# BUS.net
KiCad netlist of a schematic drawn in Altium Designer
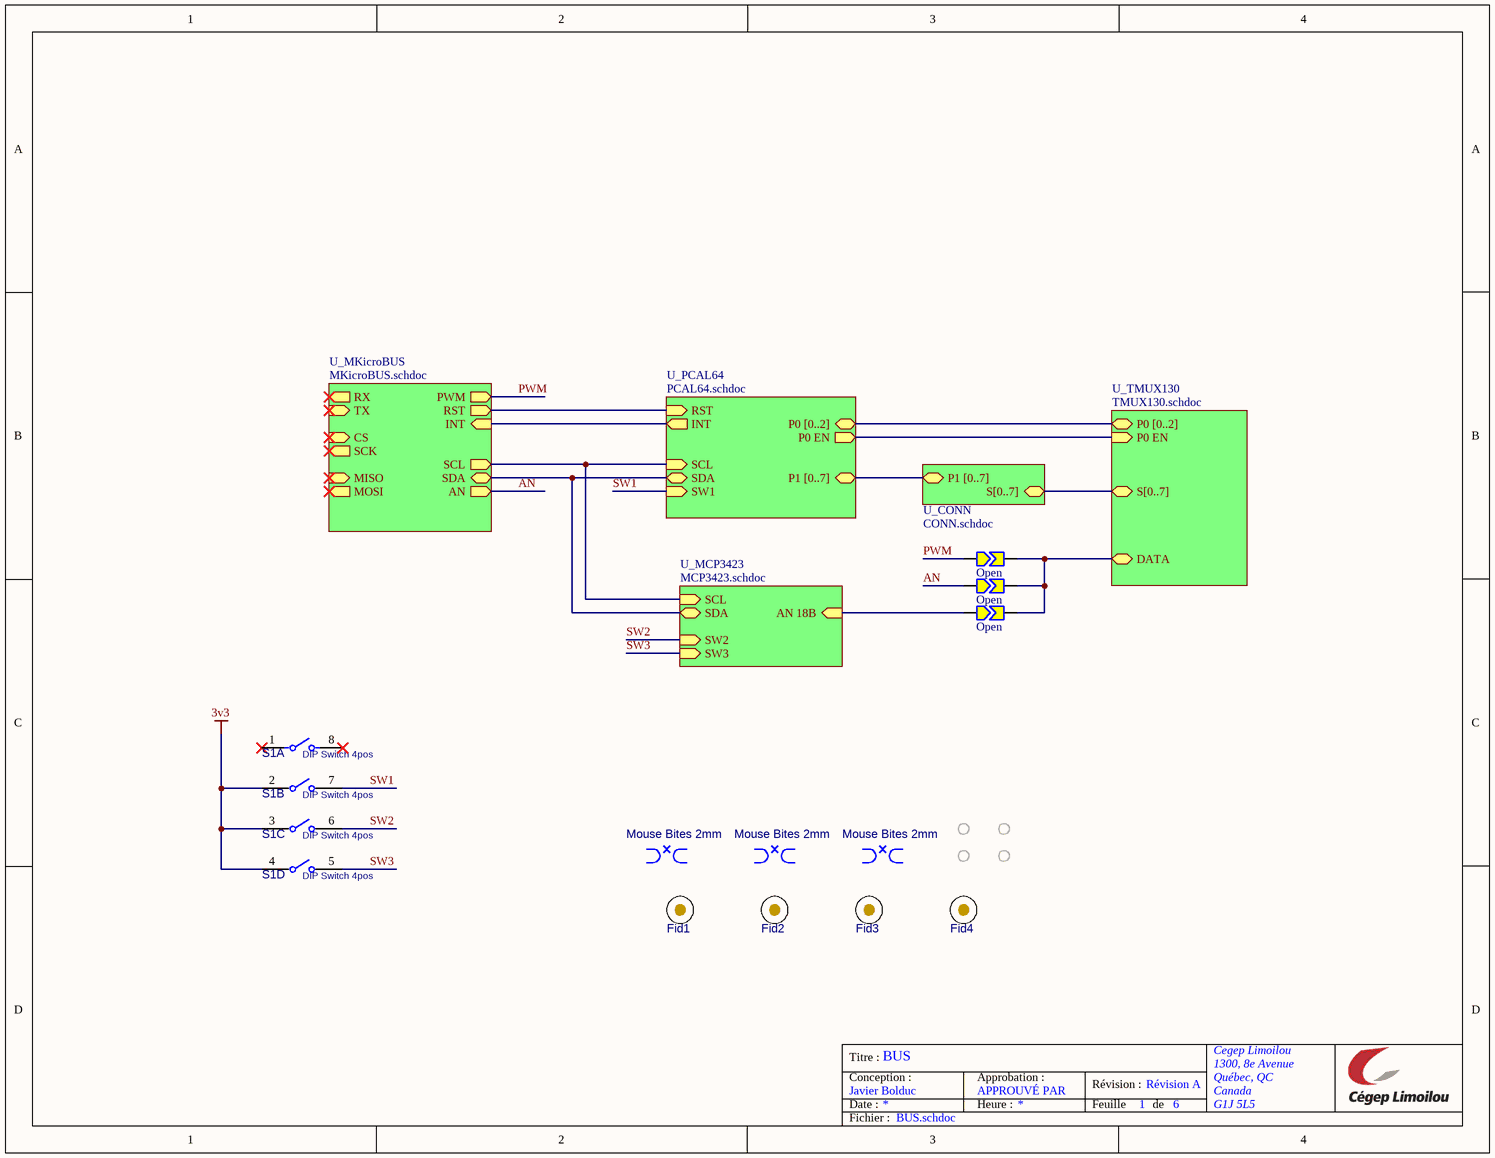
[diagram p0: BUS.schdoc]

(export (version "E")
  (design (tool "Eeschema 10.0.6"))
  (components
    (comp (ref "BRK1")
      (value "Mouse Bites 2mm")
      (footprint "BK_CRACK1B_M")
      (description "Mouse Bites")
      (fields (field (name "Comment") "DNP"))
      (libsource (lib "TEP-AltiumLib-Hardware") (part "BK_BREAKOUT_2MM"))
    )
    (comp (ref "BRK3")
      (value "Mouse Bites 2mm")
      (footprint "BK_CRACK1B_M")
      (description "Mouse Bites")
      (fields (field (name "Comment") "DNP"))
      (libsource (lib "TEP-AltiumLib-Hardware") (part "BK_BREAKOUT_2MM"))
    )
    (comp (ref "BRK4")
      (value "Mouse Bites 2mm")
      (footprint "BK_CRACK1B_M")
      (description "Mouse Bites")
      (fields (field (name "Comment") "DNP"))
      (libsource (lib "TEP-AltiumLib-Hardware") (part "BK_BREAKOUT_2MM"))
    )
    (comp (ref "Fid1")
      (value "DNP")
      (footprint "FD_Fiducial")
      (description "Fiducial mark for alignement and Pick&Place")
      (libsource (lib "TEP-AltiumLib-TP-MH-Tooling-Logo") (part "Fiducial"))
    )
    (comp (ref "Fid2")
      (value "DNP")
      (footprint "FD_Fiducial")
      (description "Fiducial mark for alignement and Pick&Place")
      (libsource (lib "TEP-AltiumLib-TP-MH-Tooling-Logo") (part "Fiducial"))
    )
    (comp (ref "Fid3")
      (value "DNP")
      (footprint "FD_Fiducial")
      (description "Fiducial mark for alignement and Pick&Place")
      (libsource (lib "TEP-AltiumLib-TP-MH-Tooling-Logo") (part "Fiducial"))
    )
    (comp (ref "Fid4")
      (value "DNP")
      (footprint "FD_Fiducial")
      (description "Fiducial mark for alignement and Pick&Place")
      (libsource (lib "TEP-AltiumLib-TP-MH-Tooling-Logo") (part "Fiducial"))
    )
    (comp (ref "MH1")
      (value "DNP")
      (footprint "MP_M-Hole_M2-NonPlated")
      (description "Mounting Hole 2mm non plated")
      (libsource (lib "TEP-AltiumLib-Hardware") (part "MH-2MM_NP"))
    )
    (comp (ref "MH2")
      (value "DNP")
      (footprint "MP_M-Hole_M2-NonPlated")
      (description "Mounting Hole 2mm non plated")
      (libsource (lib "TEP-AltiumLib-Hardware") (part "MH-2MM_NP"))
    )
    (comp (ref "MH3")
      (value "DNP")
      (footprint "MP_M-Hole_M2-NonPlated")
      (description "Mounting Hole 2mm non plated")
      (libsource (lib "TEP-AltiumLib-Hardware") (part "MH-2MM_NP"))
    )
    (comp (ref "MH4")
      (value "DNP")
      (footprint "MP_M-Hole_M2-NonPlated")
      (description "Mounting Hole 2mm non plated")
      (libsource (lib "TEP-AltiumLib-Hardware") (part "MH-2MM_NP"))
    )
    (comp (ref "S1")
      (value "DIP Switch 4pos")
      (footprint "S_DIP_SWITCH_50MIL_4POS")
      (description "SWITCH DIP SLIDE SPST 25MA 24V, pitch 1.27mm, height 1.55mm")
      (fields (field (name "Comment") "DSHP04TSGER"))
      (libsource (lib "TEP-AltiumLib") (part "SW_DIP_50MIL_4POS"))
    )
    (comp (ref "SB1")
      (value "Open")
      (footprint "SB-TINY-OPEN")
      (description "Solder Jumper")
      (libsource (lib "TEP-AltiumLib-Hardware") (part "Solder-Jumper-Open"))
    )
    (comp (ref "SB2")
      (value "Open")
      (footprint "SB-TINY-OPEN")
      (description "Solder Jumper")
      (libsource (lib "TEP-AltiumLib-Hardware") (part "Solder-Jumper-Open"))
    )
    (comp (ref "SB3")
      (value "Open")
      (footprint "SB-TINY-OPEN")
      (description "Solder Jumper")
      (libsource (lib "TEP-AltiumLib-Hardware") (part "Solder-Jumper-Open"))
    )
  )
  (nets
    (net (code "1") (name "/AN") (class "Default")
      (node (ref "SB2") (pin "1") (pinfunction "1_1") (pintype "passive"))
    )
    (net (code "2") (name "/AN 18B") (class "Default")
      (node (ref "SB3") (pin "1") (pinfunction "1_1") (pintype "passive"))
    )
    (net (code "4") (name "/DATA") (class "Default")
      (node (ref "SB1") (pin "2") (pinfunction "2_2") (pintype "passive"))
      (node (ref "SB2") (pin "2") (pinfunction "2_2") (pintype "passive"))
      (node (ref "SB3") (pin "2") (pinfunction "2_2") (pintype "passive"))
    )
    (net (code "11") (name "/PWM") (class "Default")
      (node (ref "SB1") (pin "1") (pinfunction "1_1") (pintype "passive"))
    )
    (net (code "17") (name "/SW1") (class "Default")
      (node (ref "S1") (pin "7") (pinfunction "7_7") (pintype "passive"))
    )
    (net (code "18") (name "/SW2") (class "Default")
      (node (ref "S1") (pin "6") (pinfunction "6_6") (pintype "passive"))
    )
    (net (code "19") (name "/SW3") (class "Default")
      (node (ref "S1") (pin "5") (pinfunction "5_5") (pintype "passive"))
    )
    (net (code "22") (name "3v3") (class "Default")
      (node (ref "S1") (pin "2") (pinfunction "2_2") (pintype "passive"))
      (node (ref "S1") (pin "3") (pinfunction "3_3") (pintype "passive"))
      (node (ref "S1") (pin "4") (pinfunction "4_4") (pintype "passive"))
    )
    (net (code "23") (name "unconnected-(BRK1-Pad1)") (class "Default")
      (node (ref "BRK1") (pin "1") (pinfunction "1_1") (pintype "passive"))
    )
    (net (code "24") (name "unconnected-(BRK1-Pad2)") (class "Default")
      (node (ref "BRK1") (pin "2") (pinfunction "2_2") (pintype "passive"))
    )
    (net (code "25") (name "unconnected-(BRK1-Pad3)") (class "Default")
      (node (ref "BRK1") (pin "3") (pinfunction "3_3") (pintype "passive"))
    )
    (net (code "26") (name "unconnected-(BRK1-Pad4)") (class "Default")
      (node (ref "BRK1") (pin "4") (pinfunction "4_4") (pintype "passive"))
    )
    (net (code "27") (name "unconnected-(BRK1-Pad5)") (class "Default")
      (node (ref "BRK1") (pin "5") (pinfunction "5_5") (pintype "passive"))
    )
    (net (code "28") (name "unconnected-(BRK3-Pad1)") (class "Default")
      (node (ref "BRK3") (pin "1") (pinfunction "1_1") (pintype "passive"))
    )
    (net (code "29") (name "unconnected-(BRK3-Pad2)") (class "Default")
      (node (ref "BRK3") (pin "2") (pinfunction "2_2") (pintype "passive"))
    )
    (net (code "30") (name "unconnected-(BRK3-Pad3)") (class "Default")
      (node (ref "BRK3") (pin "3") (pinfunction "3_3") (pintype "passive"))
    )
    (net (code "31") (name "unconnected-(BRK3-Pad4)") (class "Default")
      (node (ref "BRK3") (pin "4") (pinfunction "4_4") (pintype "passive"))
    )
    (net (code "32") (name "unconnected-(BRK3-Pad5)") (class "Default")
      (node (ref "BRK3") (pin "5") (pinfunction "5_5") (pintype "passive"))
    )
    (net (code "33") (name "unconnected-(BRK4-Pad1)") (class "Default")
      (node (ref "BRK4") (pin "1") (pinfunction "1_1") (pintype "passive"))
    )
    (net (code "34") (name "unconnected-(BRK4-Pad2)") (class "Default")
      (node (ref "BRK4") (pin "2") (pinfunction "2_2") (pintype "passive"))
    )
    (net (code "35") (name "unconnected-(BRK4-Pad3)") (class "Default")
      (node (ref "BRK4") (pin "3") (pinfunction "3_3") (pintype "passive"))
    )
    (net (code "36") (name "unconnected-(BRK4-Pad4)") (class "Default")
      (node (ref "BRK4") (pin "4") (pinfunction "4_4") (pintype "passive"))
    )
    (net (code "37") (name "unconnected-(BRK4-Pad5)") (class "Default")
      (node (ref "BRK4") (pin "5") (pinfunction "5_5") (pintype "passive"))
    )
    (net (code "38") (name "unconnected-(Fid1-Pad1)") (class "Default")
      (node (ref "Fid1") (pin "1") (pinfunction "1_1") (pintype "passive"))
    )
    (net (code "39") (name "unconnected-(Fid1-Pad1)_1") (class "Default")
      (node (ref "Fid1") (pin "1") (pinfunction "1_1") (pintype "passive"))
    )
    (net (code "40") (name "unconnected-(Fid1-Pad2)") (class "Default")
      (node (ref "Fid1") (pin "2") (pinfunction "2_2") (pintype "passive"))
    )
    (net (code "41") (name "unconnected-(Fid1-Pad3)") (class "Default")
      (node (ref "Fid1") (pin "3") (pinfunction "3_3") (pintype "passive"))
    )
    (net (code "42") (name "unconnected-(Fid1-Pad4)") (class "Default")
      (node (ref "Fid1") (pin "4") (pinfunction "4_4") (pintype "passive"))
    )
    (net (code "43") (name "unconnected-(Fid1-Pad5)") (class "Default")
      (node (ref "Fid1") (pin "5") (pinfunction "5_5") (pintype "passive"))
    )
    (net (code "44") (name "unconnected-(Fid2-Pad1)") (class "Default")
      (node (ref "Fid2") (pin "1") (pinfunction "1_1") (pintype "passive"))
    )
    (net (code "45") (name "unconnected-(Fid2-Pad1)_1") (class "Default")
      (node (ref "Fid2") (pin "1") (pinfunction "1_1") (pintype "passive"))
    )
    (net (code "46") (name "unconnected-(Fid2-Pad2)") (class "Default")
      (node (ref "Fid2") (pin "2") (pinfunction "2_2") (pintype "passive"))
    )
    (net (code "47") (name "unconnected-(Fid2-Pad3)") (class "Default")
      (node (ref "Fid2") (pin "3") (pinfunction "3_3") (pintype "passive"))
    )
    (net (code "48") (name "unconnected-(Fid2-Pad4)") (class "Default")
      (node (ref "Fid2") (pin "4") (pinfunction "4_4") (pintype "passive"))
    )
    (net (code "49") (name "unconnected-(Fid2-Pad5)") (class "Default")
      (node (ref "Fid2") (pin "5") (pinfunction "5_5") (pintype "passive"))
    )
    (net (code "50") (name "unconnected-(Fid3-Pad1)") (class "Default")
      (node (ref "Fid3") (pin "1") (pinfunction "1_1") (pintype "passive"))
    )
    (net (code "51") (name "unconnected-(Fid3-Pad1)_1") (class "Default")
      (node (ref "Fid3") (pin "1") (pinfunction "1_1") (pintype "passive"))
    )
    (net (code "52") (name "unconnected-(Fid3-Pad2)") (class "Default")
      (node (ref "Fid3") (pin "2") (pinfunction "2_2") (pintype "passive"))
    )
    (net (code "53") (name "unconnected-(Fid3-Pad3)") (class "Default")
      (node (ref "Fid3") (pin "3") (pinfunction "3_3") (pintype "passive"))
    )
    (net (code "54") (name "unconnected-(Fid3-Pad4)") (class "Default")
      (node (ref "Fid3") (pin "4") (pinfunction "4_4") (pintype "passive"))
    )
    (net (code "55") (name "unconnected-(Fid3-Pad5)") (class "Default")
      (node (ref "Fid3") (pin "5") (pinfunction "5_5") (pintype "passive"))
    )
    (net (code "56") (name "unconnected-(Fid4-Pad1)") (class "Default")
      (node (ref "Fid4") (pin "1") (pinfunction "1_1") (pintype "passive"))
    )
    (net (code "57") (name "unconnected-(Fid4-Pad1)_1") (class "Default")
      (node (ref "Fid4") (pin "1") (pinfunction "1_1") (pintype "passive"))
    )
    (net (code "58") (name "unconnected-(Fid4-Pad2)") (class "Default")
      (node (ref "Fid4") (pin "2") (pinfunction "2_2") (pintype "passive"))
    )
    (net (code "59") (name "unconnected-(Fid4-Pad3)") (class "Default")
      (node (ref "Fid4") (pin "3") (pinfunction "3_3") (pintype "passive"))
    )
    (net (code "60") (name "unconnected-(Fid4-Pad4)") (class "Default")
      (node (ref "Fid4") (pin "4") (pinfunction "4_4") (pintype "passive"))
    )
    (net (code "61") (name "unconnected-(Fid4-Pad5)") (class "Default")
      (node (ref "Fid4") (pin "5") (pinfunction "5_5") (pintype "passive"))
    )
    (net (code "62") (name "unconnected-(S1-Pad1)") (class "Default")
      (node (ref "S1") (pin "1") (pinfunction "1_1") (pintype "passive+no_connect"))
    )
    (net (code "63") (name "unconnected-(S1-Pad8)") (class "Default")
      (node (ref "S1") (pin "8") (pinfunction "8_8") (pintype "passive+no_connect"))
    )
  )
)
